# interface_dac_sma_feedback_2PS.net
KiCad netlist of a schematic drawn in EAGLE
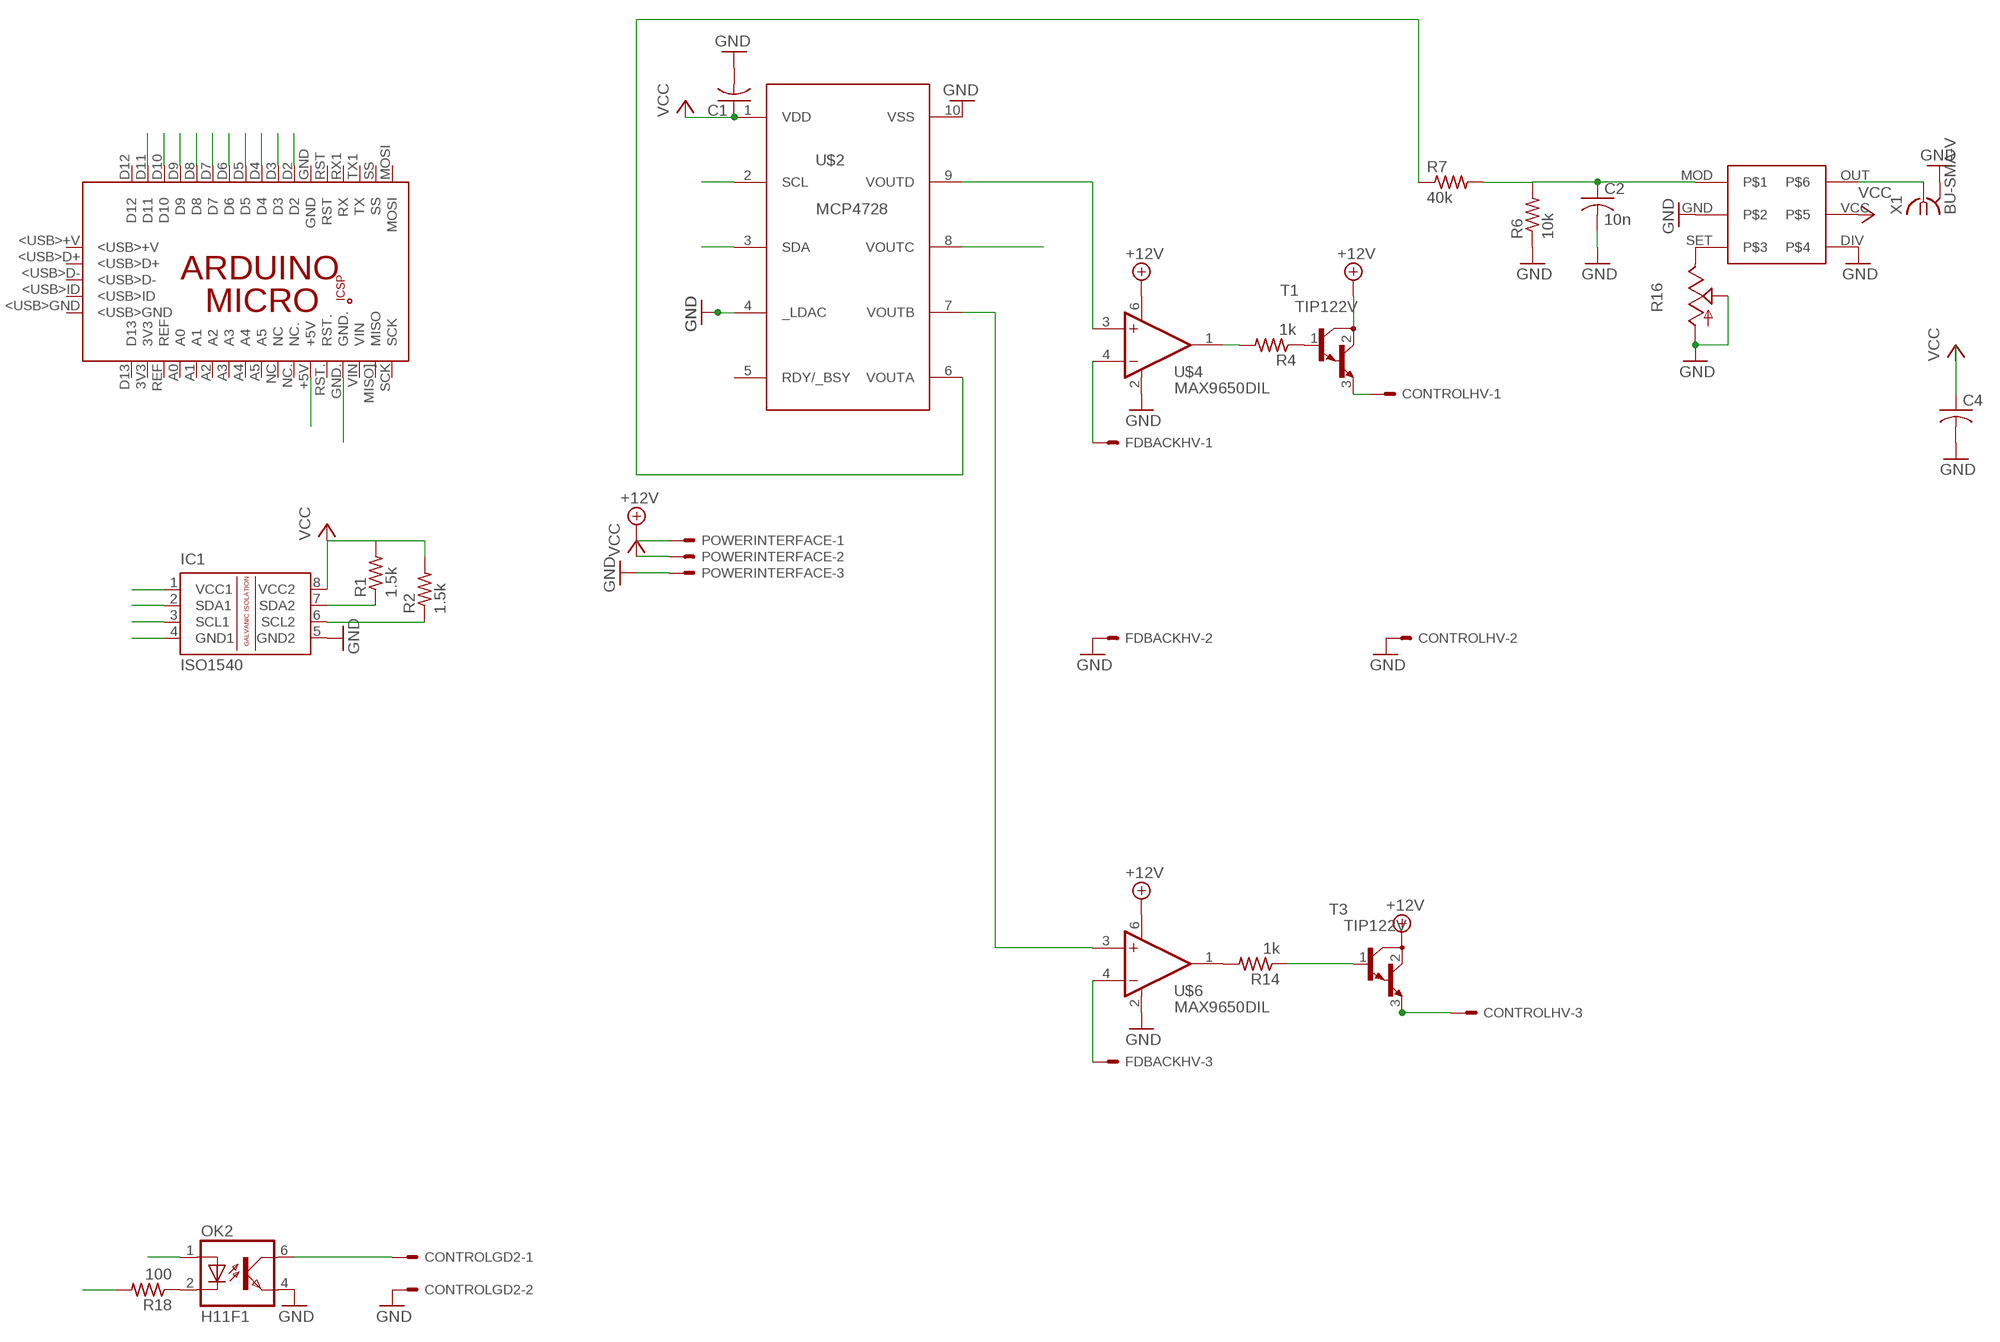
[diagram p0: schematic, sheet 1]

(export (version "E")
  (design (tool "Eeschema 10.0.6"))
  (components
    (comp (ref "C1")
      (value "C-US050-050X075")
      (footprint "eagle-import:C050-050X075")
      (libsource (lib "eagle-import") (part "C-US050-050X075"))
    )
    (comp (ref "C2")
      (value "10n")
      (footprint "eagle-import:C050-024X044")
      (libsource (lib "eagle-import") (part "resistor_C-US050-024X044"))
    )
    (comp (ref "C4")
      (value "C-US075-063X106")
      (footprint "eagle-import:C075-063X106")
      (libsource (lib "eagle-import") (part "resistor_C-US075-063X106"))
    )
    (comp (ref "CONTROLGD2")
      (value "KK-156-2")
      (footprint "eagle-import:KK-156-2")
      (libsource (lib "eagle-import") (part "KK-156-2"))
    )
    (comp (ref "CONTROLHV")
      (value "KK-156-3")
      (footprint "eagle-import:KK-156-3")
      (libsource (lib "eagle-import") (part "KK-156-3"))
    )
    (comp (ref "FDBACKHV")
      (value "KK-156-3")
      (footprint "eagle-import:KK-156-3")
      (libsource (lib "eagle-import") (part "KK-156-3"))
    )
    (comp (ref "IC1")
      (value "ISO1540")
      (footprint "eagle-import:DIL08")
      (libsource (lib "eagle-import") (part "ISO1540"))
    )
    (comp (ref "OK2")
      (value "H11F1")
      (footprint "eagle-import:DIL05")
      (libsource (lib "eagle-import") (part "H11F1"))
    )
    (comp (ref "PCB1")
      (value "ARDUINO_MICRO")
      (footprint "eagle-import:ARDUINO_MICRO")
      (libsource (lib "eagle-import") (part "ARDUINO_MICRO"))
    )
    (comp (ref "POWERINTERFACE")
      (value "KK-156-3")
      (footprint "eagle-import:KK-156-3")
      (libsource (lib "eagle-import") (part "KK-156-3"))
    )
    (comp (ref "R1")
      (value "1.5k")
      (footprint "eagle-import:0207_12")
      (libsource (lib "eagle-import") (part "resistor_R-US_0207/12"))
    )
    (comp (ref "R2")
      (value "1.5k")
      (footprint "eagle-import:0207_12")
      (libsource (lib "eagle-import") (part "resistor_R-US_0207/12"))
    )
    (comp (ref "R4")
      (value "1k")
      (footprint "eagle-import:0207_12")
      (libsource (lib "eagle-import") (part "resistor_R-US_0207/12"))
    )
    (comp (ref "R6")
      (value "10k")
      (footprint "eagle-import:0207_12")
      (libsource (lib "eagle-import") (part "resistor_R-US_0207/12"))
    )
    (comp (ref "R7")
      (value "40k")
      (footprint "eagle-import:0207_12")
      (libsource (lib "eagle-import") (part "resistor_R-US_0207/12"))
    )
    (comp (ref "R14")
      (value "1k")
      (footprint "eagle-import:0207_12")
      (libsource (lib "eagle-import") (part "resistor_R-US_0207/12"))
    )
    (comp (ref "R16")
      (value "TRIM_US-B90P")
      (footprint "eagle-import:SP19L")
      (libsource (lib "eagle-import") (part "TRIM_US-B90P"))
    )
    (comp (ref "R18")
      (value "100")
      (footprint "eagle-import:0207_12")
      (libsource (lib "eagle-import") (part "R-US_0207/12"))
    )
    (comp (ref "T1")
      (value "TIP122V")
      (footprint "eagle-import:TO220V")
      (libsource (lib "eagle-import") (part "TIP122V"))
    )
    (comp (ref "T3")
      (value "TIP122V")
      (footprint "eagle-import:TO220V")
      (libsource (lib "eagle-import") (part "TIP122V"))
    )
    (comp (ref "U$1")
      (value "LTC6992")
      (footprint "eagle-import:DIL06")
      (libsource (lib "eagle-import") (part "LTC6992"))
    )
    (comp (ref "U$2")
      (value "MCP4728DIL")
      (footprint "eagle-import:DIL10")
      (libsource (lib "eagle-import") (part "MCP4728DIL"))
    )
    (comp (ref "U$4")
      (value "MAX9650DIL")
      (footprint "eagle-import:DIL06-4")
      (libsource (lib "eagle-import") (part "MAX9650DIL"))
    )
    (comp (ref "U$6")
      (value "MAX9650DIL")
      (footprint "eagle-import:DIL06-4")
      (libsource (lib "eagle-import") (part "MAX9650DIL"))
    )
    (comp (ref "X1")
      (value "BU-SMA-V")
      (footprint "eagle-import:BU-SMA-V")
      (libsource (lib "eagle-import") (part "BU-SMA-V"))
    )
  )
  (nets
    (net (code "1") (name "+12V") (class "Default")
      (node (ref "POWERINTERFACE") (pin "1") (pinfunction "S_1") (pintype "passive"))
      (node (ref "T1") (pin "2") (pinfunction "C_2") (pintype "passive"))
      (node (ref "T3") (pin "2") (pinfunction "C_2") (pintype "passive"))
      (node (ref "U$4") (pin "6") (pinfunction "V+_6") (pintype "power_in"))
      (node (ref "U$6") (pin "6") (pinfunction "V+_6") (pintype "power_in"))
    )
    (net (code "2") (name "/A+5") (class "Default")
      (node (ref "IC1") (pin "1") (pinfunction "VCC1_1") (pintype "input"))
      (node (ref "PCB1") (pin "+5V") (pinfunction "+5V_+5V") (pintype "bidirectional"))
    )
    (net (code "3") (name "/AGND") (class "Default")
      (node (ref "IC1") (pin "4") (pinfunction "GND1_4") (pintype "input"))
      (node (ref "PCB1") (pin "GND.") (pinfunction "GND._GND.") (pintype "bidirectional"))
      (node (ref "R18") (pin "2") (pinfunction "2_2") (pintype "passive"))
    )
    (net (code "4") (name "/N$2") (class "Default")
      (node (ref "C2") (pin "1") (pinfunction "1_1") (pintype "passive"))
      (node (ref "R6") (pin "2") (pinfunction "2_2") (pintype "passive"))
      (node (ref "R7") (pin "2") (pinfunction "2_2") (pintype "passive"))
      (node (ref "U$1") (pin "MOD") (pinfunction "P$1_MOD") (pintype "bidirectional"))
    )
    (net (code "5") (name "/PWM9") (class "Default")
      (node (ref "OK2") (pin "1") (pinfunction "A_1") (pintype "passive"))
      (node (ref "PCB1") (pin "D9") (pinfunction "D9_D9") (pintype "bidirectional"))
    )
    (net (code "6") (name "/SCL") (class "Default")
      (node (ref "IC1") (pin "3") (pinfunction "SCL1_3") (pintype "input"))
      (node (ref "PCB1") (pin "D3") (pinfunction "D3_D3") (pintype "bidirectional"))
    )
    (net (code "7") (name "/SCL_OUT") (class "Default")
      (node (ref "IC1") (pin "6") (pinfunction "SCL2_6") (pintype "input"))
      (node (ref "R2") (pin "1") (pinfunction "1_1") (pintype "passive"))
      (node (ref "U$2") (pin "2") (pinfunction "SCL_2") (pintype "bidirectional"))
    )
    (net (code "8") (name "/SDA") (class "Default")
      (node (ref "IC1") (pin "2") (pinfunction "SDA1_2") (pintype "input"))
      (node (ref "PCB1") (pin "D2") (pinfunction "D2_D2") (pintype "bidirectional"))
    )
    (net (code "9") (name "/SDA_OUT") (class "Default")
      (node (ref "IC1") (pin "7") (pinfunction "SDA2_7") (pintype "input"))
      (node (ref "R1") (pin "1") (pinfunction "1_1") (pintype "passive"))
      (node (ref "U$2") (pin "3") (pinfunction "SDA_3") (pintype "bidirectional"))
    )
    (net (code "10") (name "GND") (class "Default")
      (node (ref "C1") (pin "2") (pinfunction "2_2") (pintype "passive"))
      (node (ref "C2") (pin "2") (pinfunction "2_2") (pintype "passive"))
      (node (ref "C4") (pin "2") (pinfunction "2_2") (pintype "passive"))
      (node (ref "CONTROLGD2") (pin "2") (pinfunction "S_2") (pintype "passive"))
      (node (ref "CONTROLHV") (pin "2") (pinfunction "S_2") (pintype "passive"))
      (node (ref "FDBACKHV") (pin "2") (pinfunction "S_2") (pintype "passive"))
      (node (ref "IC1") (pin "5") (pinfunction "GND2_5") (pintype "input"))
      (node (ref "OK2") (pin "4") (pinfunction "EMIT_4") (pintype "passive"))
      (node (ref "POWERINTERFACE") (pin "3") (pinfunction "S_3") (pintype "passive"))
      (node (ref "R16") (pin "A") (pinfunction "A_A") (pintype "passive"))
      (node (ref "R16") (pin "S") (pinfunction "S_S") (pintype "passive"))
      (node (ref "R6") (pin "1") (pinfunction "1_1") (pintype "passive"))
      (node (ref "U$1") (pin "DIV") (pinfunction "P$4_DIV") (pintype "bidirectional"))
      (node (ref "U$1") (pin "GND") (pinfunction "P$2_GND") (pintype "bidirectional"))
      (node (ref "U$2") (pin "10") (pinfunction "VSS_10") (pintype "bidirectional"))
      (node (ref "U$2") (pin "4") (pinfunction "_LDAC_4") (pintype "bidirectional"))
      (node (ref "U$4") (pin "2") (pinfunction "V-_2") (pintype "power_in"))
      (node (ref "U$6") (pin "2") (pinfunction "V-_2") (pintype "power_in"))
      (node (ref "X1") (pin "2") (pinfunction "2_2") (pintype "passive"))
      (node (ref "X1") (pin "3") (pinfunction "2_3") (pintype "passive"))
      (node (ref "X1") (pin "4") (pinfunction "2_4") (pintype "passive"))
      (node (ref "X1") (pin "5") (pinfunction "2_5") (pintype "passive"))
    )
    (net (code "11") (name "Net-(CONTROLGD2A-S)") (class "Default")
      (node (ref "CONTROLGD2") (pin "1") (pinfunction "S_1") (pintype "passive"))
      (node (ref "OK2") (pin "6") (pinfunction "COL_6") (pintype "passive"))
    )
    (net (code "12") (name "Net-(CONTROLHVA-S)") (class "Default")
      (node (ref "CONTROLHV") (pin "1") (pinfunction "S_1") (pintype "passive"))
      (node (ref "T1") (pin "3") (pinfunction "E_3") (pintype "passive"))
    )
    (net (code "13") (name "Net-(CONTROLHVC-S)") (class "Default")
      (node (ref "CONTROLHV") (pin "3") (pinfunction "S_3") (pintype "passive"))
      (node (ref "T3") (pin "3") (pinfunction "E_3") (pintype "passive"))
    )
    (net (code "14") (name "Net-(FDBACKHVA-S)") (class "Default")
      (node (ref "FDBACKHV") (pin "1") (pinfunction "S_1") (pintype "passive"))
      (node (ref "U$4") (pin "4") (pinfunction "-IN_4") (pintype "input"))
    )
    (net (code "15") (name "Net-(FDBACKHVC-S)") (class "Default")
      (node (ref "FDBACKHV") (pin "3") (pinfunction "S_3") (pintype "passive"))
      (node (ref "U$6") (pin "4") (pinfunction "-IN_4") (pintype "input"))
    )
    (net (code "16") (name "Net-(OK2-C)") (class "Default")
      (node (ref "OK2") (pin "2") (pinfunction "C_2") (pintype "passive"))
      (node (ref "R18") (pin "1") (pinfunction "1_1") (pintype "passive"))
    )
    (net (code "17") (name "Net-(T1-B)") (class "Default")
      (node (ref "R4") (pin "1") (pinfunction "1_1") (pintype "passive"))
      (node (ref "T1") (pin "1") (pinfunction "B_1") (pintype "passive"))
    )
    (net (code "18") (name "Net-(T3-B)") (class "Default")
      (node (ref "R14") (pin "1") (pinfunction "1_1") (pintype "passive"))
      (node (ref "T3") (pin "1") (pinfunction "B_1") (pintype "passive"))
    )
    (net (code "19") (name "Net-(U$1-P$3)") (class "Default")
      (node (ref "R16") (pin "E") (pinfunction "E_E") (pintype "passive"))
      (node (ref "U$1") (pin "SET") (pinfunction "P$3_SET") (pintype "bidirectional"))
    )
    (net (code "20") (name "Net-(U$1-P$6)") (class "Default")
      (node (ref "U$1") (pin "OUT") (pinfunction "P$6_OUT") (pintype "bidirectional"))
      (node (ref "X1") (pin "1") (pinfunction "1_1") (pintype "passive"))
    )
    (net (code "21") (name "Net-(U$2-VOUTA)") (class "Default")
      (node (ref "R7") (pin "1") (pinfunction "1_1") (pintype "passive"))
      (node (ref "U$2") (pin "6") (pinfunction "VOUTA_6") (pintype "bidirectional"))
    )
    (net (code "22") (name "Net-(U$2-VOUTB)") (class "Default")
      (node (ref "U$2") (pin "7") (pinfunction "VOUTB_7") (pintype "bidirectional"))
      (node (ref "U$6") (pin "3") (pinfunction "+IN_3") (pintype "input"))
    )
    (net (code "23") (name "Net-(U$2-VOUTD)") (class "Default")
      (node (ref "U$2") (pin "9") (pinfunction "VOUTD_9") (pintype "bidirectional"))
      (node (ref "U$4") (pin "3") (pinfunction "+IN_3") (pintype "input"))
    )
    (net (code "24") (name "Net-(U$4-OUT)") (class "Default")
      (node (ref "R4") (pin "2") (pinfunction "2_2") (pintype "passive"))
      (node (ref "U$4") (pin "1") (pinfunction "OUT_1") (pintype "output"))
    )
    (net (code "25") (name "Net-(U$6-OUT)") (class "Default")
      (node (ref "R14") (pin "2") (pinfunction "2_2") (pintype "passive"))
      (node (ref "U$6") (pin "1") (pinfunction "OUT_1") (pintype "output"))
    )
    (net (code "26") (name "VCC") (class "Default")
      (node (ref "C1") (pin "1") (pinfunction "1_1") (pintype "passive"))
      (node (ref "C4") (pin "1") (pinfunction "1_1") (pintype "passive"))
      (node (ref "IC1") (pin "8") (pinfunction "VCC2_8") (pintype "input"))
      (node (ref "POWERINTERFACE") (pin "2") (pinfunction "S_2") (pintype "passive"))
      (node (ref "R1") (pin "2") (pinfunction "2_2") (pintype "passive"))
      (node (ref "R2") (pin "2") (pinfunction "2_2") (pintype "passive"))
      (node (ref "U$1") (pin "VCC") (pinfunction "P$5_VCC") (pintype "bidirectional"))
      (node (ref "U$2") (pin "1") (pinfunction "VDD_1") (pintype "bidirectional"))
    )
    (net (code "27") (name "unconnected-(PCB1-MISO-PadMISO])") (class "Default")
      (node (ref "PCB1") (pin "MISO]") (pinfunction "MISO_MISO]") (pintype "bidirectional"))
    )
    (net (code "28") (name "unconnected-(PCB1-Pad3V3)") (class "Default")
      (node (ref "PCB1") (pin "3V3") (pinfunction "3V3_3V3") (pintype "bidirectional"))
    )
    (net (code "29") (name "unconnected-(PCB1-Pad5V)") (class "Default")
      (node (ref "PCB1") (pin "5V") (pinfunction "5V_5V") (pintype "bidirectional"))
    )
    (net (code "30") (name "unconnected-(PCB1-Pad<USB>+V)") (class "Default")
      (node (ref "PCB1") (pin "<USB>+V") (pinfunction "<USB>+V_<USB>+V") (pintype "bidirectional"))
    )
    (net (code "31") (name "unconnected-(PCB1-Pad<USB>D+)") (class "Default")
      (node (ref "PCB1") (pin "<USB>D+") (pinfunction "<USB>D+_<USB>D+") (pintype "bidirectional"))
    )
    (net (code "32") (name "unconnected-(PCB1-Pad<USB>D-)") (class "Default")
      (node (ref "PCB1") (pin "<USB>D-") (pinfunction "<USB>D-_<USB>D-") (pintype "bidirectional"))
    )
    (net (code "33") (name "unconnected-(PCB1-Pad<USB>GND)") (class "Default")
      (node (ref "PCB1") (pin "<USB>GND") (pinfunction "<USB>GND_<USB>GND") (pintype "bidirectional"))
    )
    (net (code "34") (name "unconnected-(PCB1-Pad<USB>ID)") (class "Default")
      (node (ref "PCB1") (pin "<USB>ID") (pinfunction "<USB>ID_<USB>ID") (pintype "bidirectional"))
    )
    (net (code "35") (name "unconnected-(PCB1-PadA0)") (class "Default")
      (node (ref "PCB1") (pin "A0") (pinfunction "A0_A0") (pintype "bidirectional"))
    )
    (net (code "36") (name "unconnected-(PCB1-PadA1)") (class "Default")
      (node (ref "PCB1") (pin "A1") (pinfunction "A1_A1") (pintype "bidirectional"))
    )
    (net (code "37") (name "unconnected-(PCB1-PadA2)") (class "Default")
      (node (ref "PCB1") (pin "A2") (pinfunction "A2_A2") (pintype "bidirectional"))
    )
    (net (code "38") (name "unconnected-(PCB1-PadA3)") (class "Default")
      (node (ref "PCB1") (pin "A3") (pinfunction "A3_A3") (pintype "bidirectional"))
    )
    (net (code "39") (name "unconnected-(PCB1-PadA4)") (class "Default")
      (node (ref "PCB1") (pin "A4") (pinfunction "A4_A4") (pintype "bidirectional"))
    )
    (net (code "40") (name "unconnected-(PCB1-PadA5)") (class "Default")
      (node (ref "PCB1") (pin "A5") (pinfunction "A5_A5") (pintype "bidirectional"))
    )
    (net (code "41") (name "unconnected-(PCB1-PadD4)") (class "Default")
      (node (ref "PCB1") (pin "D4") (pinfunction "D4_D4") (pintype "bidirectional"))
    )
    (net (code "42") (name "unconnected-(PCB1-PadD5)") (class "Default")
      (node (ref "PCB1") (pin "D5") (pinfunction "D5_D5") (pintype "bidirectional"))
    )
    (net (code "43") (name "unconnected-(PCB1-PadD6)") (class "Default")
      (node (ref "PCB1") (pin "D6") (pinfunction "D6_D6") (pintype "bidirectional"))
    )
    (net (code "44") (name "unconnected-(PCB1-PadD7)") (class "Default")
      (node (ref "PCB1") (pin "D7") (pinfunction "D7_D7") (pintype "bidirectional"))
    )
    (net (code "45") (name "unconnected-(PCB1-PadD8)") (class "Default")
      (node (ref "PCB1") (pin "D8") (pinfunction "D8_D8") (pintype "bidirectional"))
    )
    (net (code "46") (name "unconnected-(PCB1-PadD10)") (class "Default")
      (node (ref "PCB1") (pin "D10") (pinfunction "D10_D10") (pintype "bidirectional"))
    )
    (net (code "47") (name "unconnected-(PCB1-PadD11)") (class "Default")
      (node (ref "PCB1") (pin "D11") (pinfunction "D11_D11") (pintype "bidirectional"))
    )
    (net (code "48") (name "unconnected-(PCB1-PadD12)") (class "Default")
      (node (ref "PCB1") (pin "D12") (pinfunction "D12_D12") (pintype "bidirectional"))
    )
    (net (code "49") (name "unconnected-(PCB1-PadD13)") (class "Default")
      (node (ref "PCB1") (pin "D13") (pinfunction "D13_D13") (pintype "bidirectional"))
    )
    (net (code "50") (name "unconnected-(PCB1-PadGND)") (class "Default")
      (node (ref "PCB1") (pin "GND") (pinfunction "GND_GND") (pintype "bidirectional"))
    )
    (net (code "51") (name "unconnected-(PCB1-PadGND_)") (class "Default")
      (node (ref "PCB1") (pin "GND_") (pinfunction "GND__GND_") (pintype "bidirectional"))
    )
    (net (code "52") (name "unconnected-(PCB1-PadMISO.)") (class "Default")
      (node (ref "PCB1") (pin "MISO.") (pinfunction "MISO._MISO.") (pintype "bidirectional"))
    )
    (net (code "53") (name "unconnected-(PCB1-PadMOSI)") (class "Default")
      (node (ref "PCB1") (pin "MOSI") (pinfunction "MOSI_MOSI") (pintype "bidirectional"))
    )
    (net (code "54") (name "unconnected-(PCB1-PadMOSI.)") (class "Default")
      (node (ref "PCB1") (pin "MOSI.") (pinfunction "MOSI._MOSI.") (pintype "bidirectional"))
    )
    (net (code "55") (name "unconnected-(PCB1-PadNC)") (class "Default")
      (node (ref "PCB1") (pin "NC") (pinfunction "NC_NC") (pintype "bidirectional"))
    )
    (net (code "56") (name "unconnected-(PCB1-PadNC.)") (class "Default")
      (node (ref "PCB1") (pin "NC.") (pinfunction "NC._NC.") (pintype "bidirectional"))
    )
    (net (code "57") (name "unconnected-(PCB1-PadREF)") (class "Default")
      (node (ref "PCB1") (pin "REF") (pinfunction "REF_REF") (pintype "bidirectional"))
    )
    (net (code "58") (name "unconnected-(PCB1-PadRESET..)") (class "Default")
      (node (ref "PCB1") (pin "RESET..") (pinfunction "RESET.._RESET..") (pintype "bidirectional"))
    )
    (net (code "59") (name "unconnected-(PCB1-PadRST)") (class "Default")
      (node (ref "PCB1") (pin "RST") (pinfunction "RST_RST") (pintype "bidirectional"))
    )
    (net (code "60") (name "unconnected-(PCB1-PadRST.)") (class "Default")
      (node (ref "PCB1") (pin "RST.") (pinfunction "RST._RST.") (pintype "bidirectional"))
    )
    (net (code "61") (name "unconnected-(PCB1-PadSCK)") (class "Default")
      (node (ref "PCB1") (pin "SCK") (pinfunction "SCK_SCK") (pintype "bidirectional"))
    )
    (net (code "62") (name "unconnected-(PCB1-PadSCK.)") (class "Default")
      (node (ref "PCB1") (pin "SCK.") (pinfunction "SCK._SCK.") (pintype "bidirectional"))
    )
    (net (code "63") (name "unconnected-(PCB1-PadSS)") (class "Default")
      (node (ref "PCB1") (pin "SS") (pinfunction "SS_SS") (pintype "bidirectional"))
    )
    (net (code "64") (name "unconnected-(PCB1-PadVIN)") (class "Default")
      (node (ref "PCB1") (pin "VIN") (pinfunction "VIN_VIN") (pintype "bidirectional"))
    )
    (net (code "65") (name "unconnected-(PCB1-RX-PadRX1)") (class "Default")
      (node (ref "PCB1") (pin "RX1") (pinfunction "RX_RX1") (pintype "bidirectional"))
    )
    (net (code "66") (name "unconnected-(PCB1-TX-PadTX1)") (class "Default")
      (node (ref "PCB1") (pin "TX1") (pinfunction "TX_TX1") (pintype "bidirectional"))
    )
    (net (code "67") (name "unconnected-(U$2-RDY{slash}_BSY-Pad5)") (class "Default")
      (node (ref "U$2") (pin "5") (pinfunction "RDY/_BSY_5") (pintype "bidirectional"))
    )
    (net (code "68") (name "unconnected-(U$2-VOUTC-Pad8)") (class "Default")
      (node (ref "U$2") (pin "8") (pinfunction "VOUTC_8") (pintype "bidirectional"))
    )
  )
)
